# PowerInput.net
KiCad netlist of a schematic drawn in Altium Designer
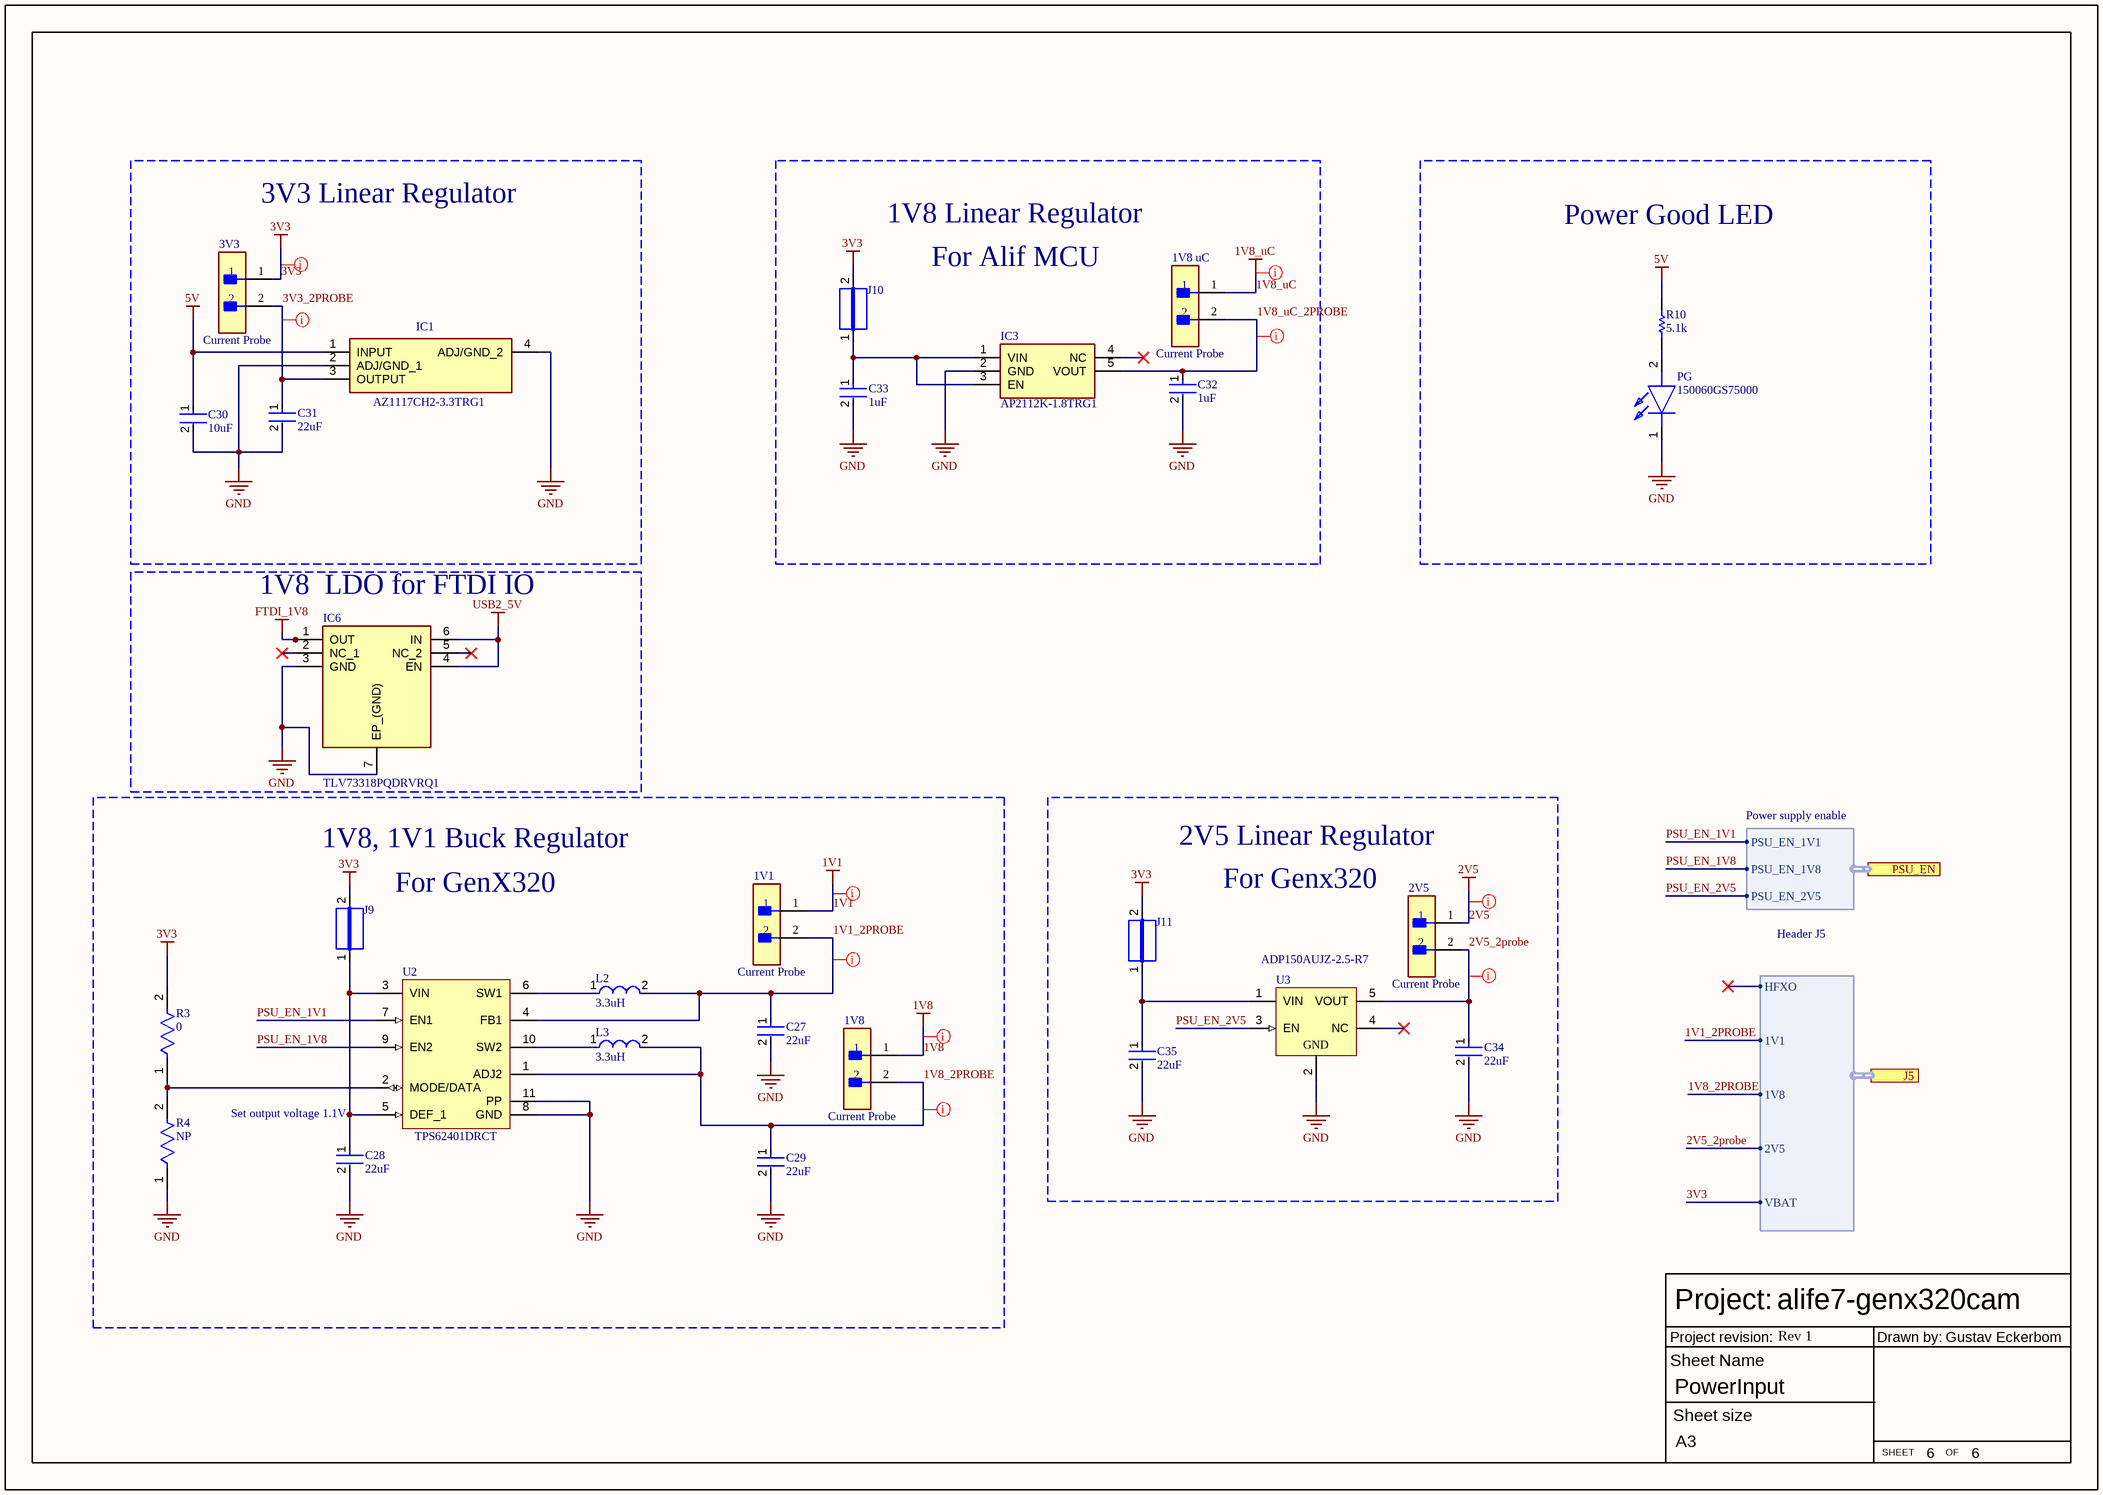
[diagram p0: PowerInput.SchDoc]

(export (version "E")
  (design (tool "Eeschema 10.0.6"))
  (components
    (comp (ref "1V1")
      (value "Current Probe")
      (footprint "FP-4-103185-0-02-MFG")
      (description "4-103185-0-02 Conn Header Vert 2POS 2.54MM")
      (libsource (lib "Altium Content Vault") (part "3bc925449376181038e59eaffc5286c"))
    )
    (comp (ref "1V8")
      (value "Current Probe")
      (footprint "FP-4-103185-0-02-MFG")
      (description "4-103185-0-02 Conn Header Vert 2POS 2.54MM")
      (libsource (lib "Altium Content Vault") (part "3bc925449376181038e59eaffc5286c"))
    )
    (comp (ref "1V8 uC")
      (value "Current Probe")
      (footprint "FP-4-103185-0-02-MFG")
      (description "4-103185-0-02 Conn Header Vert 2POS 2.54MM")
      (libsource (lib "Altium Content Vault") (part "3bc925449376181038e59eaffc5286c"))
    )
    (comp (ref "2V5")
      (value "Current Probe")
      (footprint "FP-4-103185-0-02-MFG")
      (description "4-103185-0-02 Conn Header Vert 2POS 2.54MM")
      (libsource (lib "Altium Content Vault") (part "3bc925449376181038e59eaffc5286c"))
    )
    (comp (ref "3V3")
      (value "Current Probe")
      (footprint "FP-4-103185-0-02-MFG")
      (description "4-103185-0-02 Conn Header Vert 2POS 2.54MM")
      (libsource (lib "Altium Content Vault") (part "3bc925449376181038e59eaffc5286c"))
    )
    (comp (ref "C27")
      (value "22uF")
      (footprint "FP-1206-L_3_2_0_2-W_1_6_0-IPC_C")
      (libsource (lib "Gustav Eckerbom") (part "b4654b650e69147ec39a6b967a45e02"))
    )
    (comp (ref "C28")
      (value "22uF")
      (footprint "FP-1206-L_3_2_0_2-W_1_6_0-IPC_C")
      (libsource (lib "Gustav Eckerbom") (part "b4654b650e69147ec39a6b967a45e02"))
    )
    (comp (ref "C29")
      (value "22uF")
      (footprint "FP-1206-L_3_2_0_2-W_1_6_0-IPC_C")
      (libsource (lib "Gustav Eckerbom") (part "b4654b650e69147ec39a6b967a45e02"))
    )
    (comp (ref "C30")
      (value "10uF")
      (footprint "FP-CC0603-0_15-0_95-IPC_C")
      (libsource (lib "Gustav Eckerbom") (part "02cd4be3c70576c341d710602a673aa"))
    )
    (comp (ref "C31")
      (value "22uF")
      (footprint "FP-1206-L_3_2_0_2-W_1_6_0-IPC_C")
      (libsource (lib "Gustav Eckerbom") (part "b4654b650e69147ec39a6b967a45e02"))
    )
    (comp (ref "C32")
      (value "1uF")
      (footprint "FP-CL10-IPC_C")
      (libsource (lib "Gustav Eckerbom") (part "b4654b650e69147ec39a6b967a45e02"))
    )
    (comp (ref "C33")
      (value "1uF")
      (footprint "FP-CL10-IPC_C")
      (libsource (lib "Gustav Eckerbom") (part "b4654b650e69147ec39a6b967a45e02"))
    )
    (comp (ref "C34")
      (value "22uF")
      (footprint "FP-1206-L_3_2_0_2-W_1_6_0-IPC_C")
      (libsource (lib "Gustav Eckerbom") (part "b4654b650e69147ec39a6b967a45e02"))
    )
    (comp (ref "C35")
      (value "22uF")
      (footprint "FP-1206-L_3_2_0_2-W_1_6_0-IPC_C")
      (libsource (lib "Gustav Eckerbom") (part "b4654b650e69147ec39a6b967a45e02"))
    )
    (comp (ref "IC1")
      (value "AZ1117CH2-3.3TRG1")
      (footprint "SamacSys:SOT230P700X180-4N")
      (description "Integrated Circuit")
      (fields (field (name "MOUSER PART NUMBER") "621-AZ1117CH2-33TRG1"))
      (libsource (lib "*") (part "AZ1117CH2-3.3TRG1"))
    )
    (comp (ref "IC3")
      (value "AP2112K-1.8TRG1")
      (footprint "SamacSys:SOT95P285X140-5N")
      (description "Integrated Circuit")
      (fields (field (name "MOUSER PART NUMBER") "621-AP2112K-1.8TRG1"))
      (libsource (lib "*") (part "AP2112K-1.8TRG1"))
    )
    (comp (ref "IC6")
      (value "TLV73318PQDRVRQ1")
      (footprint "SamacSys:SON65P200X200X80-7N")
      (description "Integrated Circuit")
      (fields (field (name "MOUSER PART NUMBER") "595-TLV73318PQDRVRQ1"))
      (libsource (lib "SamacSys") (part "TLV73318PQDRVRQ1"))
    )
    (comp (ref "J9")
      (value "JUMPER")
      (footprint "JUMPER")
      (libsource (lib "Gustav Eckerbom") (part "JUMPER"))
    )
    (comp (ref "J10")
      (value "JUMPER")
      (footprint "JUMPER")
      (libsource (lib "Gustav Eckerbom") (part "JUMPER"))
    )
    (comp (ref "J11")
      (value "JUMPER")
      (footprint "JUMPER")
      (libsource (lib "Gustav Eckerbom") (part "JUMPER"))
    )
    (comp (ref "L2")
      (value "3.3uH")
      (footprint "FP-LQM21PH_G0-IPC_C")
      (description "Multilayer Type Inductor for Power Lines, 0805 (2012), 3.3μH, 30%, 0.207Ω, 0.8A")
      (fields (field (name "TOLERANCE") "30%"))
      (libsource (lib "Altium Content Vault") (part "725321dda6339637d4d059423bc1c3c"))
    )
    (comp (ref "L3")
      (value "3.3uH")
      (footprint "FP-LQM21PH_G0-IPC_C")
      (description "Multilayer Type Inductor for Power Lines, 0805 (2012), 3.3μH, 30%, 0.207Ω, 0.8A")
      (fields (field (name "TOLERANCE") "30%"))
      (libsource (lib "Altium Content Vault") (part "725321dda6339637d4d059423bc1c3c"))
    )
    (comp (ref "PG")
      (value "150060GS75000")
      (footprint "SamacSys:LEDC1608X80N")
      (description "LED")
      (fields (field (name "MOUSER PART NUMBER") "710-150060GS75000"))
      (libsource (lib "*") (part "150060GS75000"))
    )
    (comp (ref "R3")
      (value "0")
      (footprint "FP-RK73Z2A-MFG")
      (description "RES 0 OHM JUMPER 0805")
      (fields (field (name "TOLERANCE") "1%"))
      (libsource (lib "Altium Content Vault") (part "1029c3af85768c4190bb7ad29bc67b5"))
    )
    (comp (ref "R4")
      (value "NP")
      (footprint "FP-RK73Z2A-MFG")
      (description "RES 0 OHM JUMPER 0805")
      (fields (field (name "TOLERANCE") "1%"))
      (libsource (lib "Altium Content Vault") (part "1029c3af85768c4190bb7ad29bc67b5"))
    )
    (comp (ref "R10")
      (value "5.1k")
      (footprint "RESC0603(1608)_N")
      (description "2K 0.1W 5% 0603 (1608 Metric)  SMD")
      (fields (field (name "TOLERANCE") "5 %") (field (name "POWER") "0.1 W"))
      (libsource (lib "Altium Content Vault") (part "RES"))
    )
    (comp (ref "U2")
      (value "TPS62401DRCT")
      (footprint "DRC0010J_V")
      (fields (field (name "MANUFACTURER") "Texas Instruments"))
      (libsource (lib "Altium Content Vault") (part "TI-TPS62401DRC10-2400X1650TP"))
    )
    (comp (ref "U3")
      (value "ADP150AUJZ-2.5-R7")
      (footprint "ADI-UJ-5_N")
      (fields (field (name "MANUFACTURER") "Analog Devices"))
      (libsource (lib "Altium Content Vault") (part "ADI-ADP1XX-UJ-5"))
    )
  )
  (nets
    (net (code "6") (name "/1V1_2PROBE") (class "Default")
      (node (ref "1V1") (pin "2") (pinfunction "2_2") (pintype "passive"))
      (node (ref "C27") (pin "1") (pinfunction "1_1") (pintype "passive"))
      (node (ref "L2") (pin "2") (pinfunction "2_2") (pintype "passive"))
      (node (ref "U2") (pin "4") (pinfunction "FB1_4") (pintype "passive"))
    )
    (net (code "7") (name "/1V8_2PROBE") (class "Default")
      (node (ref "1V8") (pin "2") (pinfunction "2_2") (pintype "passive"))
      (node (ref "C29") (pin "1") (pinfunction "1_1") (pintype "passive"))
      (node (ref "L3") (pin "2") (pinfunction "2_2") (pintype "passive"))
      (node (ref "U2") (pin "1") (pinfunction "ADJ2_1") (pintype "passive"))
    )
    (net (code "8") (name "/1V8_uC_2PROBE") (class "Default")
      (node (ref "1V8 uC") (pin "2") (pinfunction "2_2") (pintype "passive"))
      (node (ref "C32") (pin "1") (pinfunction "1_1") (pintype "passive"))
      (node (ref "IC3") (pin "5") (pinfunction "VOUT_5") (pintype "passive"))
    )
    (net (code "9") (name "/2V5_2probe") (class "Default")
      (node (ref "2V5") (pin "2") (pinfunction "2_2") (pintype "passive"))
      (node (ref "C34") (pin "1") (pinfunction "1_1") (pintype "passive"))
      (node (ref "U3") (pin "5") (pinfunction "VOUT_5") (pintype "power_in"))
    )
    (net (code "10") (name "/3V3_2PROBE") (class "Default")
      (node (ref "3V3") (pin "2") (pinfunction "2_2") (pintype "passive"))
      (node (ref "C31") (pin "1") (pinfunction "1_1") (pintype "passive"))
      (node (ref "IC1") (pin "3") (pinfunction "OUTPUT_3") (pintype "passive"))
    )
    (net (code "11") (name "/PSU_EN_1V1") (class "Default")
      (node (ref "U2") (pin "7") (pinfunction "EN1_7") (pintype "input"))
    )
    (net (code "12") (name "/PSU_EN_1V8") (class "Default")
      (node (ref "U2") (pin "9") (pinfunction "EN2_9") (pintype "input"))
    )
    (net (code "13") (name "/PSU_EN_2V5") (class "Default")
      (node (ref "U3") (pin "3") (pinfunction "EN_3") (pintype "input"))
    )
    (net (code "16") (name "1V1") (class "Default")
      (node (ref "1V1") (pin "1") (pinfunction "1_1") (pintype "passive"))
    )
    (net (code "17") (name "1V8") (class "Default")
      (node (ref "1V8") (pin "1") (pinfunction "1_1") (pintype "passive"))
    )
    (net (code "18") (name "1V8_uC") (class "Default")
      (node (ref "1V8 uC") (pin "1") (pinfunction "1_1") (pintype "passive"))
    )
    (net (code "19") (name "2V5") (class "Default")
      (node (ref "2V5") (pin "1") (pinfunction "1_1") (pintype "passive"))
    )
    (net (code "20") (name "3V3") (class "Default")
      (node (ref "3V3") (pin "1") (pinfunction "1_1") (pintype "passive"))
      (node (ref "J10") (pin "2") (pinfunction "2_2") (pintype "passive"))
      (node (ref "J11") (pin "2") (pinfunction "2_2") (pintype "passive"))
      (node (ref "J9") (pin "2") (pinfunction "2_2") (pintype "passive"))
      (node (ref "R3") (pin "2") (pinfunction "2_2") (pintype "passive"))
    )
    (net (code "21") (name "5V") (class "Default")
      (node (ref "C30") (pin "1") (pinfunction "1_1") (pintype "passive"))
      (node (ref "IC1") (pin "1") (pinfunction "INPUT_1") (pintype "passive"))
      (node (ref "R10") (pin "2") (pinfunction "2_2") (pintype "passive"))
    )
    (net (code "22") (name "FTDI_1V8") (class "Default")
      (node (ref "IC6") (pin "1") (pinfunction "OUT_1") (pintype "passive"))
    )
    (net (code "23") (name "GND") (class "Default")
      (node (ref "C27") (pin "2") (pinfunction "2_2") (pintype "passive"))
      (node (ref "C28") (pin "2") (pinfunction "2_2") (pintype "passive"))
      (node (ref "C29") (pin "2") (pinfunction "2_2") (pintype "passive"))
      (node (ref "C30") (pin "2") (pinfunction "2_2") (pintype "passive"))
      (node (ref "C31") (pin "2") (pinfunction "2_2") (pintype "passive"))
      (node (ref "C32") (pin "2") (pinfunction "2_2") (pintype "passive"))
      (node (ref "C33") (pin "2") (pinfunction "2_2") (pintype "passive"))
      (node (ref "C34") (pin "2") (pinfunction "2_2") (pintype "passive"))
      (node (ref "C35") (pin "2") (pinfunction "2_2") (pintype "passive"))
      (node (ref "IC1") (pin "2") (pinfunction "ADJ/GND_1_2") (pintype "passive"))
      (node (ref "IC1") (pin "4") (pinfunction "ADJ/GND_2_4") (pintype "passive"))
      (node (ref "IC3") (pin "2") (pinfunction "GND_2") (pintype "passive"))
      (node (ref "IC6") (pin "3") (pinfunction "GND_3") (pintype "passive"))
      (node (ref "IC6") (pin "7") (pinfunction "EP_(GND)_7") (pintype "passive"))
      (node (ref "PG") (pin "1") (pinfunction "K_1") (pintype "passive"))
      (node (ref "R4") (pin "1") (pinfunction "1_1") (pintype "passive"))
      (node (ref "U2") (pin "11") (pinfunction "PP_11") (pintype "power_in"))
      (node (ref "U2") (pin "8") (pinfunction "GND_8") (pintype "power_in"))
      (node (ref "U3") (pin "2") (pinfunction "GND_2") (pintype "power_in"))
    )
    (net (code "24") (name "Net-(IC3-EN)") (class "Default")
      (node (ref "C33") (pin "1") (pinfunction "1_1") (pintype "passive"))
      (node (ref "IC3") (pin "1") (pinfunction "VIN_1") (pintype "passive"))
      (node (ref "IC3") (pin "3") (pinfunction "EN_3") (pintype "passive"))
      (node (ref "J10") (pin "1") (pinfunction "1_1") (pintype "passive"))
    )
    (net (code "25") (name "Net-(PG-A)") (class "Default")
      (node (ref "PG") (pin "2") (pinfunction "A_2") (pintype "passive"))
      (node (ref "R10") (pin "1") (pinfunction "1_1") (pintype "passive"))
    )
    (net (code "26") (name "Net-(U2-DEF_1)") (class "Default")
      (node (ref "C28") (pin "1") (pinfunction "1_1") (pintype "passive"))
      (node (ref "J9") (pin "1") (pinfunction "1_1") (pintype "passive"))
      (node (ref "U2") (pin "3") (pinfunction "VIN_3") (pintype "power_in"))
      (node (ref "U2") (pin "5") (pinfunction "DEF_1_5") (pintype "input"))
    )
    (net (code "27") (name "Net-(U2-MODE{slash}DATA)") (class "Default")
      (node (ref "R3") (pin "1") (pinfunction "1_1") (pintype "passive"))
      (node (ref "R4") (pin "2") (pinfunction "2_2") (pintype "passive"))
      (node (ref "U2") (pin "2") (pinfunction "MODE/DATA_2") (pintype "bidirectional"))
    )
    (net (code "28") (name "Net-(U2-SW1)") (class "Default")
      (node (ref "L2") (pin "1") (pinfunction "1_1") (pintype "passive"))
      (node (ref "U2") (pin "6") (pinfunction "SW1_6") (pintype "power_in"))
    )
    (net (code "29") (name "Net-(U2-SW2)") (class "Default")
      (node (ref "L3") (pin "1") (pinfunction "1_1") (pintype "passive"))
      (node (ref "U2") (pin "10") (pinfunction "SW2_10") (pintype "power_in"))
    )
    (net (code "30") (name "Net-(U3-VIN)") (class "Default")
      (node (ref "C35") (pin "1") (pinfunction "1_1") (pintype "passive"))
      (node (ref "J11") (pin "1") (pinfunction "1_1") (pintype "passive"))
      (node (ref "U3") (pin "1") (pinfunction "VIN_1") (pintype "power_in"))
    )
    (net (code "31") (name "USB2_5V") (class "Default")
      (node (ref "IC6") (pin "4") (pinfunction "EN_4") (pintype "passive"))
      (node (ref "IC6") (pin "6") (pinfunction "IN_6") (pintype "passive"))
    )
    (net (code "32") (name "unconnected-(IC3-NC-Pad4)") (class "Default")
      (node (ref "IC3") (pin "4") (pinfunction "NC_4") (pintype "passive+no_connect"))
    )
    (net (code "33") (name "unconnected-(IC6-NC_1-Pad2)") (class "Default")
      (node (ref "IC6") (pin "2") (pinfunction "NC_1_2") (pintype "passive+no_connect"))
    )
    (net (code "34") (name "unconnected-(IC6-NC_2-Pad5)") (class "Default")
      (node (ref "IC6") (pin "5") (pinfunction "NC_2_5") (pintype "passive+no_connect"))
    )
    (net (code "35") (name "unconnected-(U3-NC-Pad4)") (class "Default")
      (node (ref "U3") (pin "4") (pinfunction "NC_4") (pintype "passive+no_connect"))
    )
  )
)
